# mbedWarp.net
KiCad netlist of a schematic drawn in EAGLE
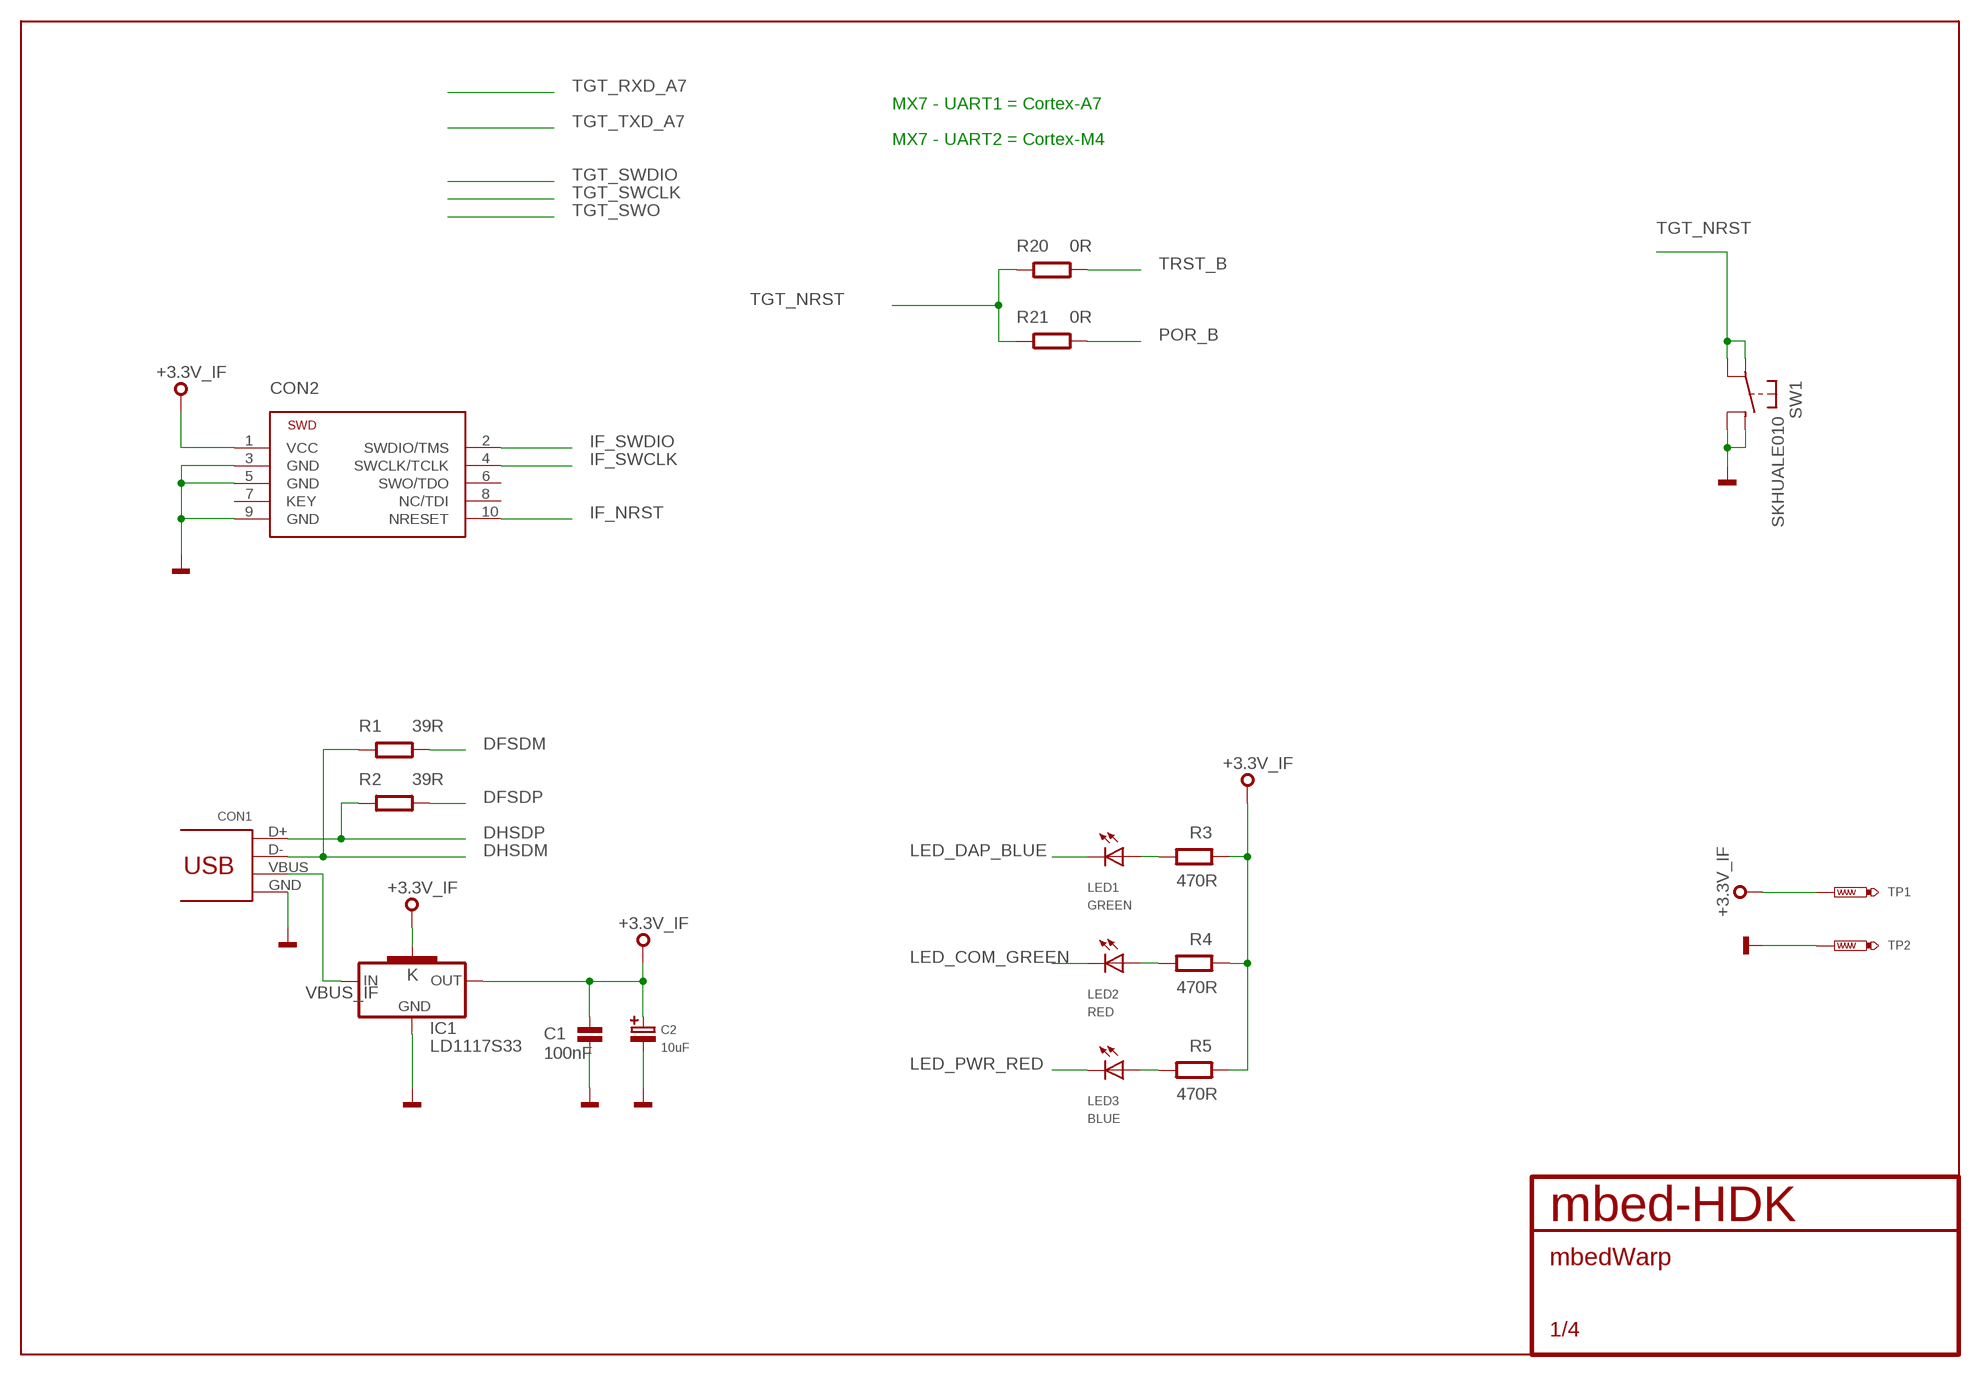
[diagram p0: schematic, sheet 1]
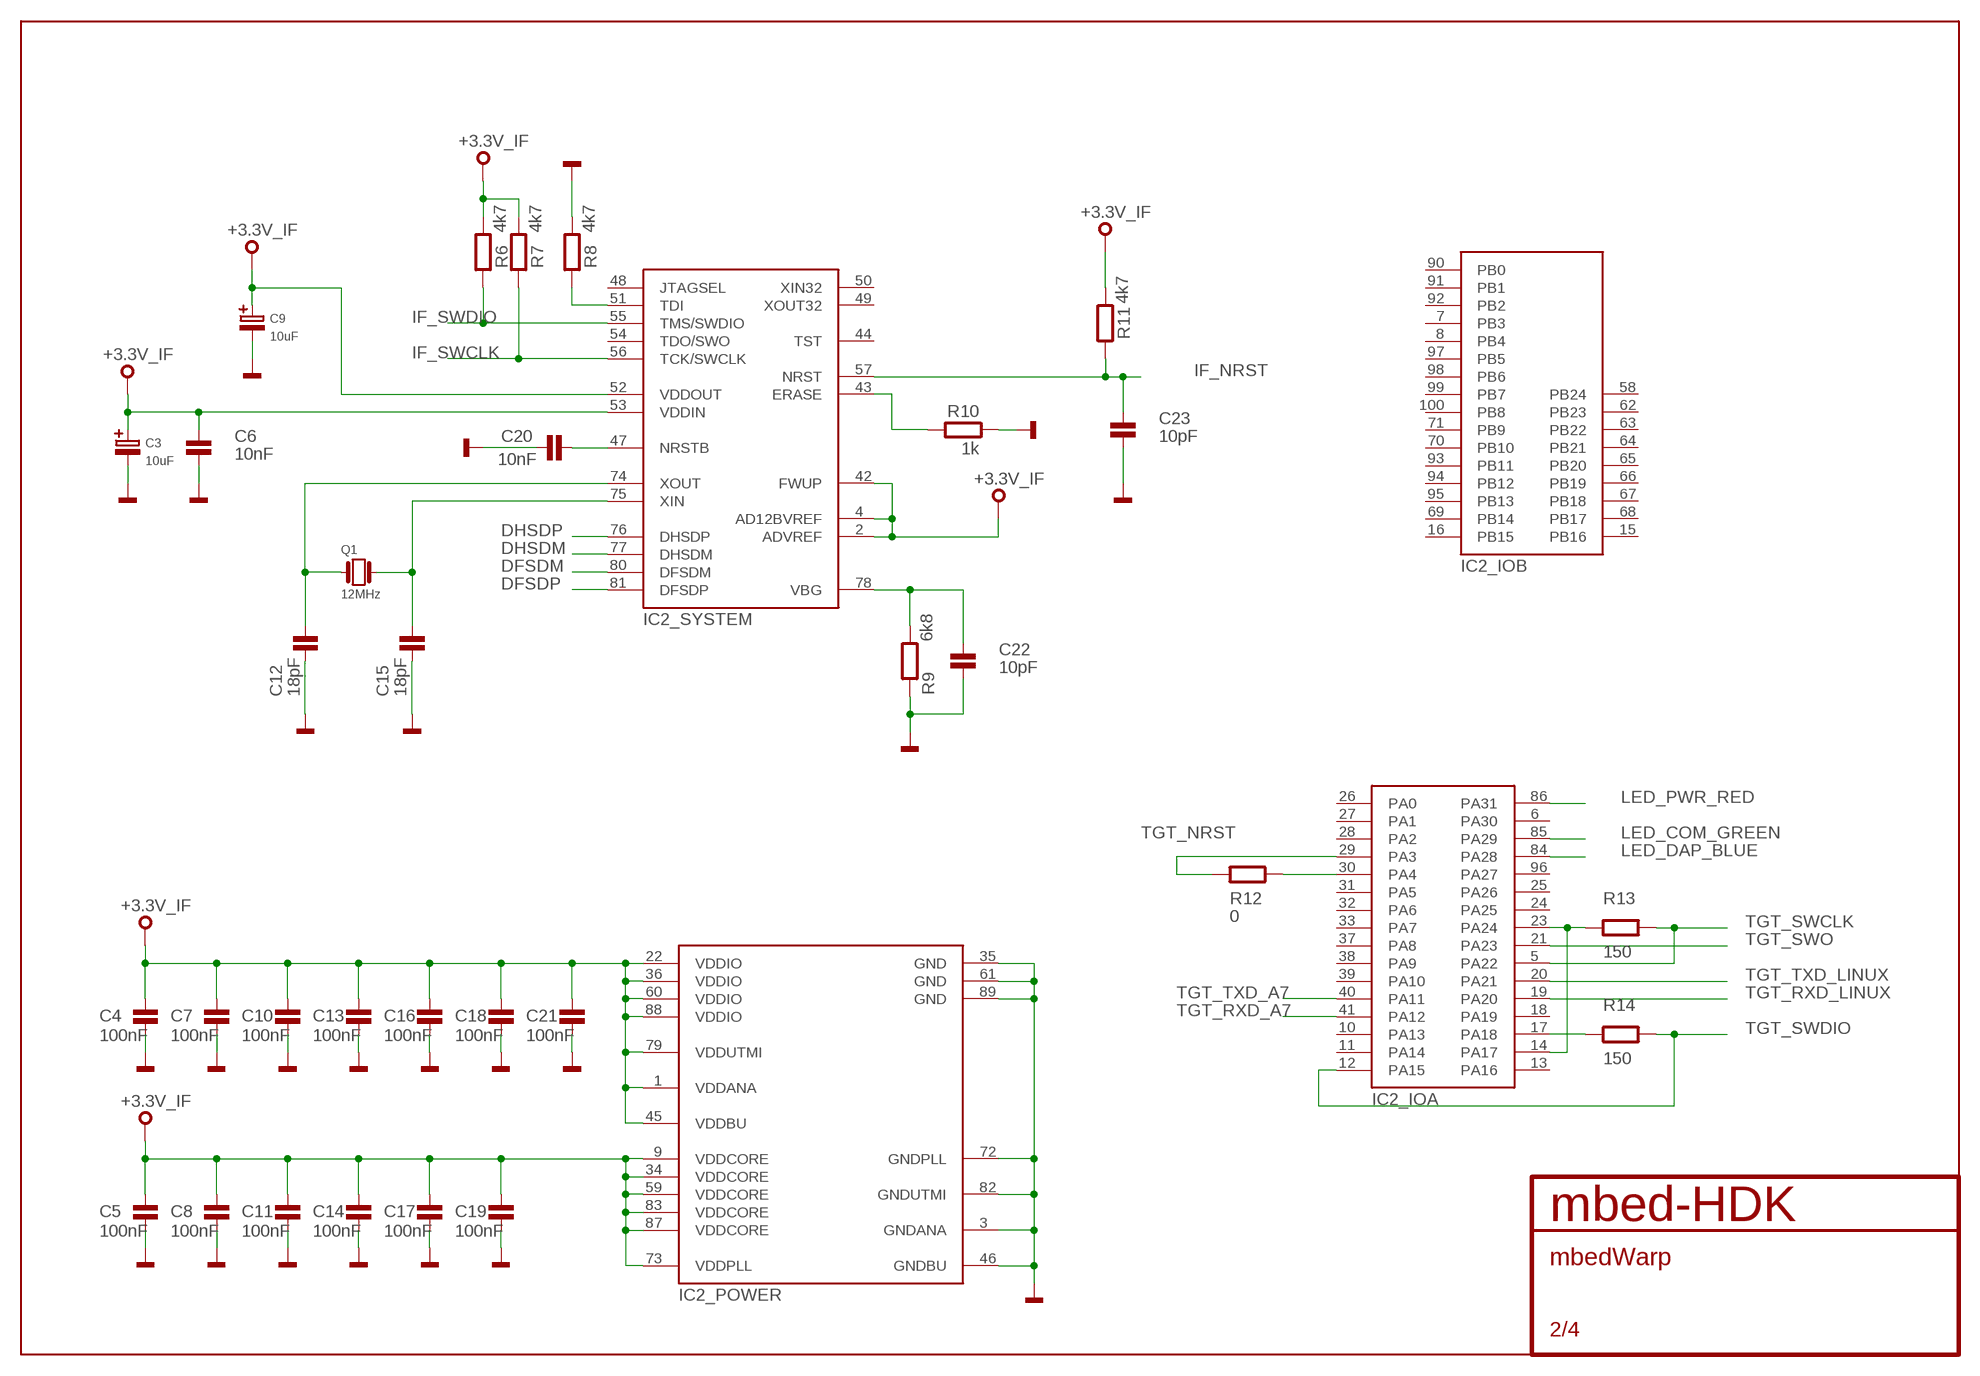
[diagram p1: schematic, sheet 2]
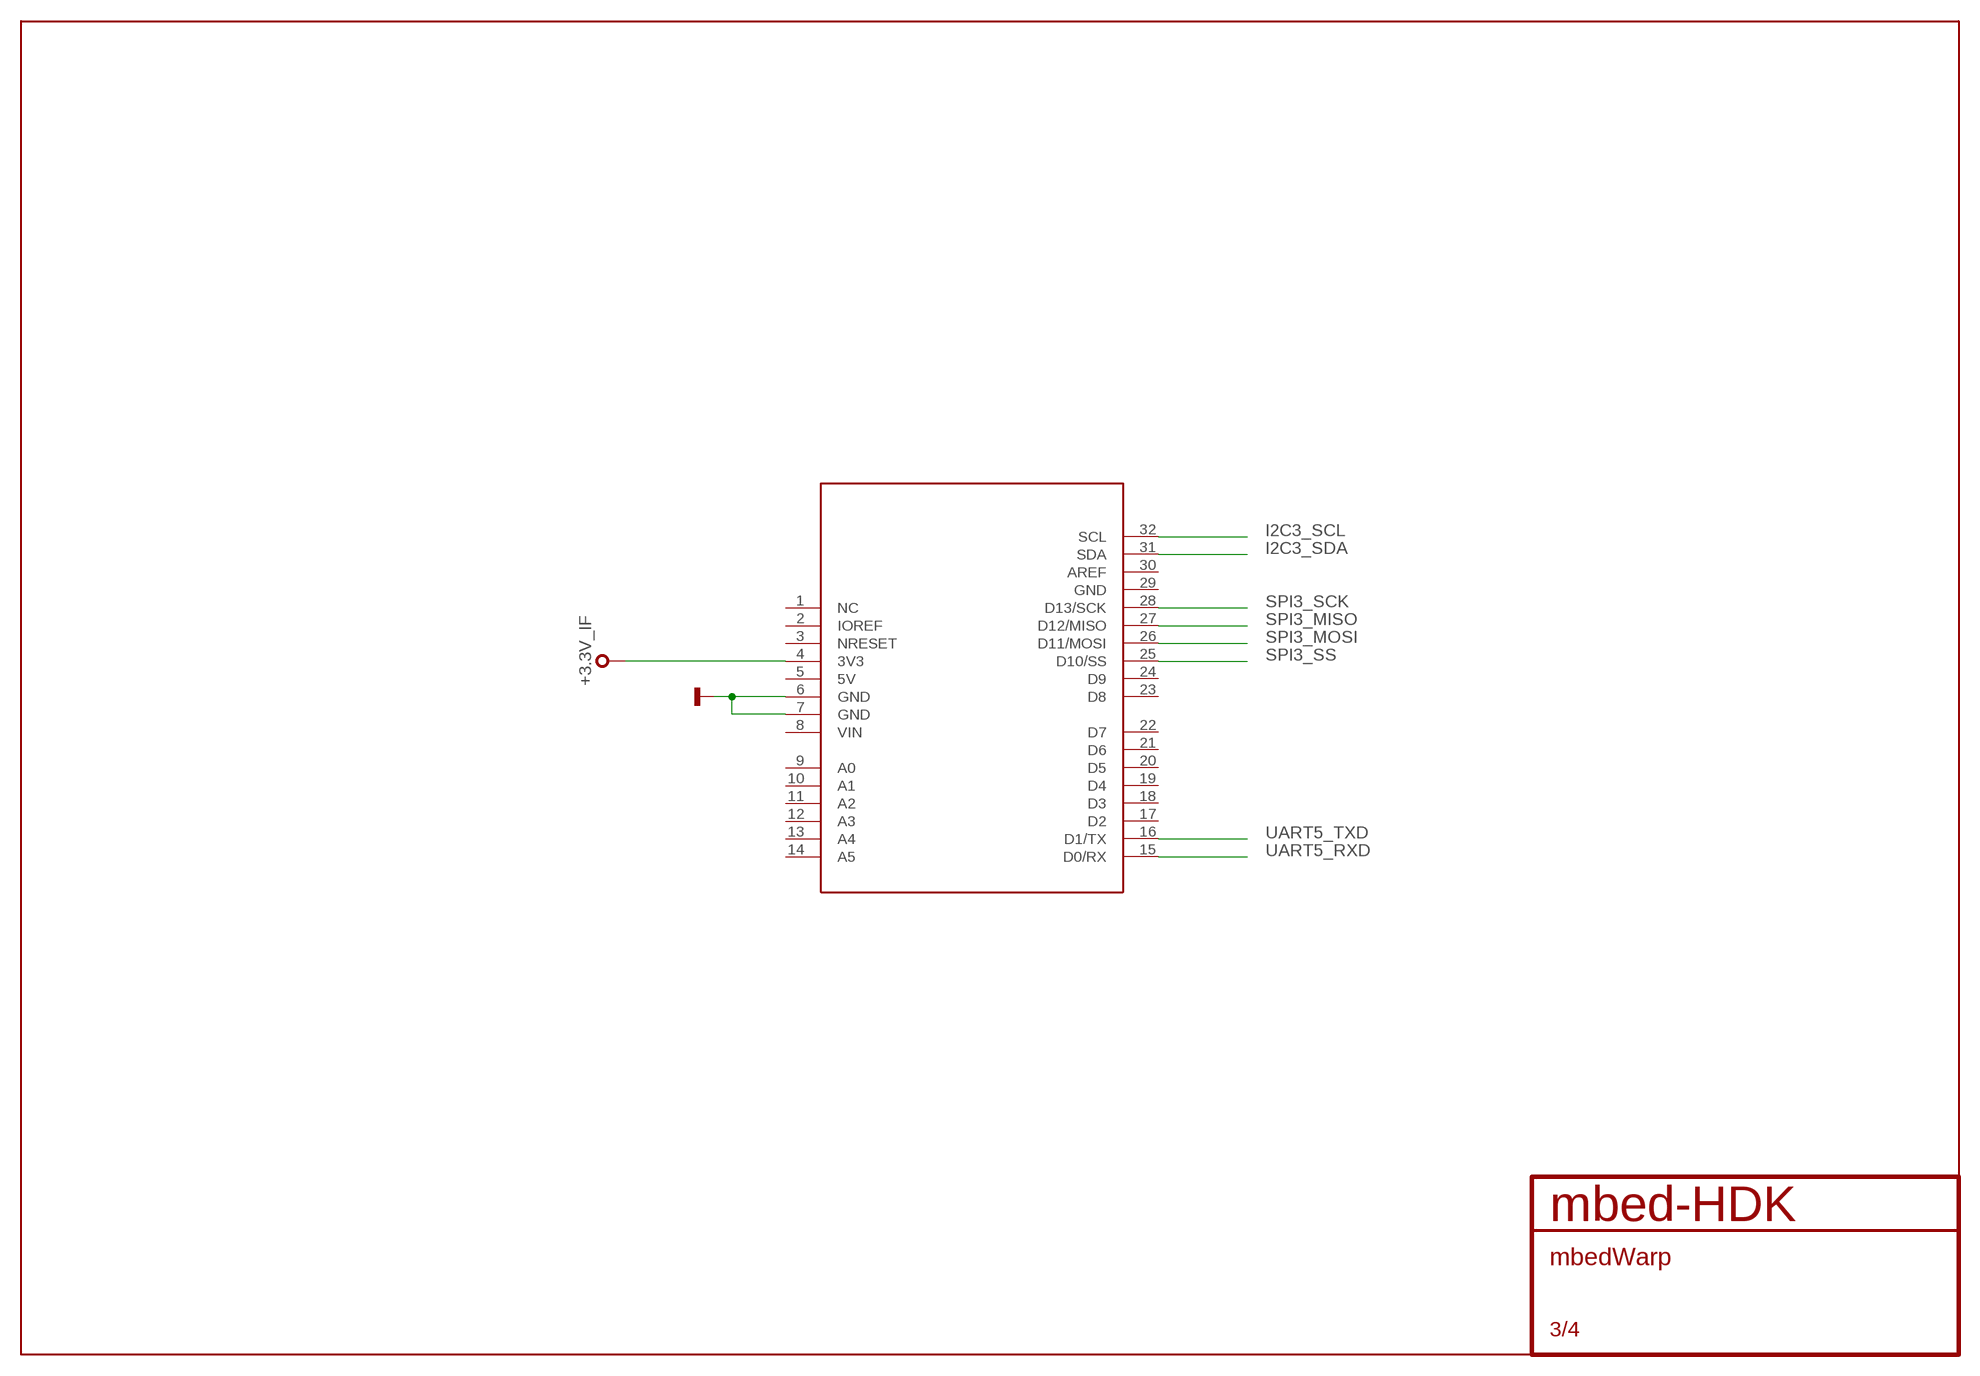
[diagram p2: schematic, sheet 3]
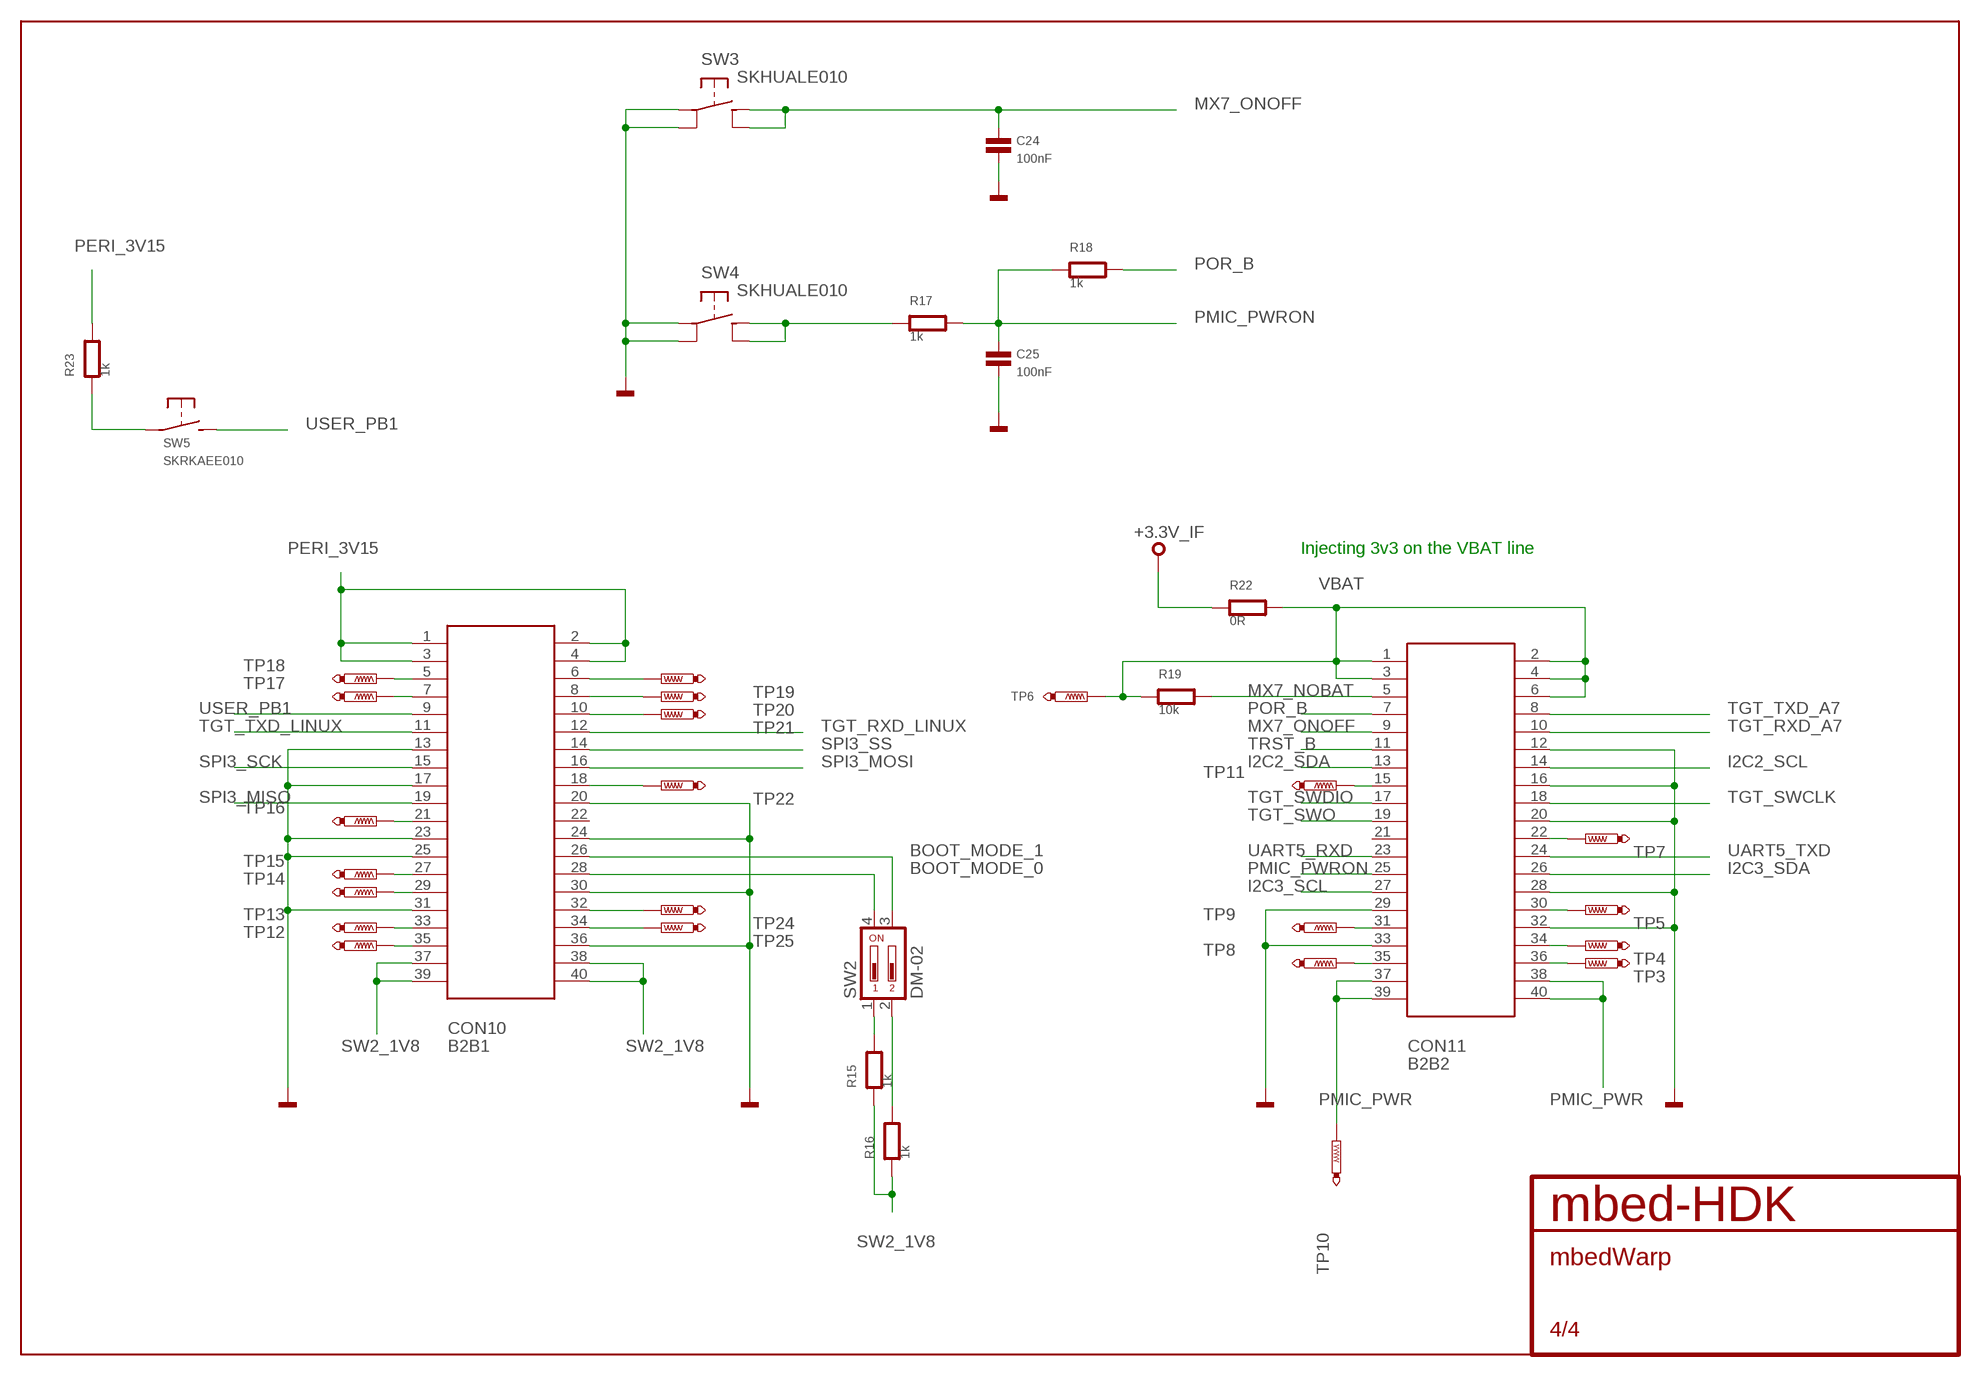
[diagram p3: schematic, sheet 4]

(export (version "E")
  (design (tool "Eeschema 10.0.6"))
  (components
    (comp (ref "C3")
      (value "10uF")
      (footprint "eagle-import:CASE-B")
      (libsource (lib "eagle-import") (part "C-POL_B"))
    )
    (comp (ref "C4")
      (value "100nF")
      (footprint "eagle-import:0603")
      (libsource (lib "eagle-import") (part "C0603"))
    )
    (comp (ref "C5")
      (value "100nF")
      (footprint "eagle-import:0603")
      (libsource (lib "eagle-import") (part "C0603"))
    )
    (comp (ref "C6")
      (value "10nF")
      (footprint "eagle-import:0603")
      (libsource (lib "eagle-import") (part "C0603"))
    )
    (comp (ref "C7")
      (value "100nF")
      (footprint "eagle-import:0603")
      (libsource (lib "eagle-import") (part "C0603"))
    )
    (comp (ref "C8")
      (value "100nF")
      (footprint "eagle-import:0603")
      (libsource (lib "eagle-import") (part "C0603"))
    )
    (comp (ref "C9")
      (value "10uF")
      (footprint "eagle-import:CASE-B")
      (libsource (lib "eagle-import") (part "C-POL_B"))
    )
    (comp (ref "C10")
      (value "100nF")
      (footprint "eagle-import:0603")
      (libsource (lib "eagle-import") (part "C0603"))
    )
    (comp (ref "C11")
      (value "100nF")
      (footprint "eagle-import:0603")
      (libsource (lib "eagle-import") (part "C0603"))
    )
    (comp (ref "C12")
      (value "18pF")
      (footprint "eagle-import:0603")
      (libsource (lib "eagle-import") (part "C0603"))
    )
    (comp (ref "C13")
      (value "100nF")
      (footprint "eagle-import:0603")
      (libsource (lib "eagle-import") (part "C0603"))
    )
    (comp (ref "C14")
      (value "100nF")
      (footprint "eagle-import:0603")
      (libsource (lib "eagle-import") (part "C0603"))
    )
    (comp (ref "C15")
      (value "18pF")
      (footprint "eagle-import:0603")
      (libsource (lib "eagle-import") (part "C0603"))
    )
    (comp (ref "C16")
      (value "100nF")
      (footprint "eagle-import:0603")
      (libsource (lib "eagle-import") (part "C0603"))
    )
    (comp (ref "C17")
      (value "100nF")
      (footprint "eagle-import:0603")
      (libsource (lib "eagle-import") (part "C0603"))
    )
    (comp (ref "C18")
      (value "100nF")
      (footprint "eagle-import:0603")
      (libsource (lib "eagle-import") (part "C0603"))
    )
    (comp (ref "C19")
      (value "100nF")
      (footprint "eagle-import:0603")
      (libsource (lib "eagle-import") (part "C0603"))
    )
    (comp (ref "C20")
      (value "10nF")
      (footprint "eagle-import:0603")
      (libsource (lib "eagle-import") (part "C0603"))
    )
    (comp (ref "C21")
      (value "100nF")
      (footprint "eagle-import:0603")
      (libsource (lib "eagle-import") (part "C0603"))
    )
    (comp (ref "C22")
      (value "10pF")
      (footprint "eagle-import:0603")
      (libsource (lib "eagle-import") (part "C0603"))
    )
    (comp (ref "C23")
      (value "10pF")
      (footprint "eagle-import:0603")
      (libsource (lib "eagle-import") (part "C0603"))
    )
    (comp (ref "IC2")
      (value "AT91SAM3U2CA")
      (footprint "eagle-import:LQFP100")
      (libsource (lib "eagle-import") (part "AT91SAM3U2CA"))
    )
    (comp (ref "Q1")
      (value "12MHz")
      (footprint "eagle-import:3.2X.2.5")
      (libsource (lib "eagle-import") (part "Q_3.2X2.5"))
    )
    (comp (ref "R6")
      (value "4k7")
      (footprint "eagle-import:0603")
      (libsource (lib "eagle-import") (part "R0603"))
    )
    (comp (ref "R7")
      (value "4k7")
      (footprint "eagle-import:0603")
      (libsource (lib "eagle-import") (part "R0603"))
    )
    (comp (ref "R8")
      (value "4k7")
      (footprint "eagle-import:0603")
      (libsource (lib "eagle-import") (part "R0603"))
    )
    (comp (ref "R9")
      (value "6k8")
      (footprint "eagle-import:0603")
      (libsource (lib "eagle-import") (part "R0603"))
    )
    (comp (ref "R10")
      (value "1k")
      (footprint "eagle-import:0603")
      (libsource (lib "eagle-import") (part "R0603"))
    )
    (comp (ref "R11")
      (value "4k7")
      (footprint "eagle-import:0603")
      (libsource (lib "eagle-import") (part "R0603"))
    )
    (comp (ref "R12")
      (value "0")
      (footprint "eagle-import:0603")
      (libsource (lib "eagle-import") (part "R0603"))
    )
    (comp (ref "R13")
      (value "150")
      (footprint "eagle-import:0603")
      (libsource (lib "eagle-import") (part "R0603"))
    )
    (comp (ref "R14")
      (value "150")
      (footprint "eagle-import:0603")
      (libsource (lib "eagle-import") (part "R0603"))
    )
    (comp (ref "C1")
      (value "100nF")
      (footprint "eagle-import:0603")
      (libsource (lib "eagle-import") (part "C0603"))
    )
    (comp (ref "C2")
      (value "10uF")
      (footprint "eagle-import:CASE-B")
      (libsource (lib "eagle-import") (part "C-POL_B"))
    )
    (comp (ref "CON1")
      (value "USB_MICROB")
      (footprint "eagle-import:MOLEX-47364-0001")
      (libsource (lib "eagle-import") (part "USB_MICROB"))
    )
    (comp (ref "CON2")
      (value "SWD-10-SMD")
      (footprint "eagle-import:SWD-10-SMD")
      (libsource (lib "eagle-import") (part "SWD-10-SMD"))
    )
    (comp (ref "IC1")
      (value "LD1117S33")
      (footprint "eagle-import:SOT223")
      (libsource (lib "eagle-import") (part "LD1117S33"))
    )
    (comp (ref "LED1")
      (value "GREEN")
      (footprint "eagle-import:CHIPLED_0603")
      (libsource (lib "eagle-import") (part "LED0603"))
    )
    (comp (ref "LED2")
      (value "RED")
      (footprint "eagle-import:CHIPLED_0603")
      (libsource (lib "eagle-import") (part "LED0603"))
    )
    (comp (ref "LED3")
      (value "BLUE")
      (footprint "eagle-import:CHIPLED_0603")
      (libsource (lib "eagle-import") (part "LED0603"))
    )
    (comp (ref "R1")
      (value "39R")
      (footprint "eagle-import:0603")
      (libsource (lib "eagle-import") (part "R0603"))
    )
    (comp (ref "R2")
      (value "39R")
      (footprint "eagle-import:0603")
      (libsource (lib "eagle-import") (part "R0603"))
    )
    (comp (ref "R3")
      (value "470R")
      (footprint "eagle-import:0603")
      (libsource (lib "eagle-import") (part "R0603"))
    )
    (comp (ref "R4")
      (value "470R")
      (footprint "eagle-import:0603")
      (libsource (lib "eagle-import") (part "R0603"))
    )
    (comp (ref "R5")
      (value "470R")
      (footprint "eagle-import:0603")
      (libsource (lib "eagle-import") (part "R0603"))
    )
    (comp (ref "R20")
      (value "0R")
      (footprint "eagle-import:0603")
      (libsource (lib "eagle-import") (part "R0603"))
    )
    (comp (ref "R21")
      (value "0R")
      (footprint "eagle-import:0603")
      (libsource (lib "eagle-import") (part "R0603"))
    )
    (comp (ref "SW1")
      (value "SKHUALE010")
      (footprint "eagle-import:SKHUALE010")
      (fields (field (name "MF") "ALPS"))
      (libsource (lib "eagle-import") (part "SKHUALE010"))
    )
    (comp (ref "TP1")
      (value "TEST-POINT-50R-PTH")
      (footprint "eagle-import:TP50-PTH")
      (libsource (lib "eagle-import") (part "TEST-POINT-50R-PTH"))
    )
    (comp (ref "TP2")
      (value "TEST-POINT-50R-PTH")
      (footprint "eagle-import:TP50-PTH")
      (libsource (lib "eagle-import") (part "TEST-POINT-50R-PTH"))
    )
    (comp (ref "BRD1")
      (value "ARDUINO-R3_SILK")
      (footprint "eagle-import:ARDUINO-R3-SILK")
      (libsource (lib "eagle-import") (part "ARDUINO-R3_SILK"))
    )
    (comp (ref "C24")
      (value "100nF")
      (footprint "eagle-import:0603")
      (libsource (lib "eagle-import") (part "CAPACITOR0603"))
    )
    (comp (ref "C25")
      (value "100nF")
      (footprint "eagle-import:0603")
      (libsource (lib "eagle-import") (part "CAPACITOR0603"))
    )
    (comp (ref "CON10")
      (value "B2B1")
      (footprint "eagle-import:DF40HC-XX-40DS-XX-V")
      (libsource (lib "eagle-import") (part "DF40HC-XX-40DS-XX-V"))
    )
    (comp (ref "CON11")
      (value "B2B2")
      (footprint "eagle-import:DF40HC-XX-40DS-XX-V")
      (libsource (lib "eagle-import") (part "DF40HC-XX-40DS-XX-V"))
    )
    (comp (ref "R15")
      (value "1k")
      (footprint "eagle-import:0603")
      (libsource (lib "eagle-import") (part "RESISTOR0603"))
    )
    (comp (ref "R16")
      (value "1k")
      (footprint "eagle-import:0603")
      (libsource (lib "eagle-import") (part "RESISTOR0603"))
    )
    (comp (ref "R17")
      (value "1k")
      (footprint "eagle-import:0603")
      (libsource (lib "eagle-import") (part "RESISTOR0603"))
    )
    (comp (ref "R18")
      (value "1k")
      (footprint "eagle-import:0603")
      (libsource (lib "eagle-import") (part "RESISTOR0603"))
    )
    (comp (ref "R19")
      (value "10k")
      (footprint "eagle-import:0603")
      (libsource (lib "eagle-import") (part "RESISTOR0603"))
    )
    (comp (ref "R22")
      (value "0R")
      (footprint "eagle-import:0603")
      (libsource (lib "eagle-import") (part "RESISTOR0603"))
    )
    (comp (ref "R23")
      (value "1k")
      (footprint "eagle-import:0603")
      (libsource (lib "eagle-import") (part "RESISTOR0603"))
    )
    (comp (ref "SW2")
      (value "DM-02")
      (footprint "eagle-import:DM-02")
      (libsource (lib "eagle-import") (part "DM-02"))
    )
    (comp (ref "SW3")
      (value "SKHUALE010")
      (footprint "eagle-import:SKHUALE010")
      (fields (field (name "MF") "ALPS"))
      (libsource (lib "eagle-import") (part "SKHUALE010"))
    )
    (comp (ref "SW4")
      (value "SKHUALE010")
      (footprint "eagle-import:SKHUALE010")
      (fields (field (name "MF") "ALPS"))
      (libsource (lib "eagle-import") (part "SKHUALE010"))
    )
    (comp (ref "SW5")
      (value "SKRKAEE010")
      (footprint "eagle-import:SKRKAEE010")
      (fields (field (name "MF") "ALPS"))
      (libsource (lib "eagle-import") (part "SKRKAEE010"))
    )
    (comp (ref "TP3")
      (value "PTR1TP06R")
      (footprint "eagle-import:TP06R")
      (libsource (lib "eagle-import") (part "PTR1TP06R"))
    )
    (comp (ref "TP4")
      (value "PTR1TP06R")
      (footprint "eagle-import:TP06R")
      (libsource (lib "eagle-import") (part "PTR1TP06R"))
    )
    (comp (ref "TP5")
      (value "PTR1TP06R")
      (footprint "eagle-import:TP06R")
      (libsource (lib "eagle-import") (part "PTR1TP06R"))
    )
    (comp (ref "TP6")
      (value "TEST-POINT-50R-SMD")
      (footprint "eagle-import:TP50-SMD")
      (libsource (lib "eagle-import") (part "TEST-POINT-50R-SMD"))
    )
    (comp (ref "TP7")
      (value "PTR1TP06R")
      (footprint "eagle-import:TP06R")
      (libsource (lib "eagle-import") (part "PTR1TP06R"))
    )
    (comp (ref "TP8")
      (value "PTR1TP06R")
      (footprint "eagle-import:TP06R")
      (libsource (lib "eagle-import") (part "PTR1TP06R"))
    )
    (comp (ref "TP9")
      (value "PTR1TP06R")
      (footprint "eagle-import:TP06R")
      (libsource (lib "eagle-import") (part "PTR1TP06R"))
    )
    (comp (ref "TP10")
      (value "PTR1TP06R")
      (footprint "eagle-import:TP06R")
      (libsource (lib "eagle-import") (part "PTR1TP06R"))
    )
    (comp (ref "TP11")
      (value "PTR1TP06R")
      (footprint "eagle-import:TP06R")
      (libsource (lib "eagle-import") (part "PTR1TP06R"))
    )
    (comp (ref "TP12")
      (value "PTR1TP06R")
      (footprint "eagle-import:TP06R")
      (libsource (lib "eagle-import") (part "PTR1TP06R"))
    )
    (comp (ref "TP13")
      (value "PTR1TP06R")
      (footprint "eagle-import:TP06R")
      (libsource (lib "eagle-import") (part "PTR1TP06R"))
    )
    (comp (ref "TP14")
      (value "PTR1TP06R")
      (footprint "eagle-import:TP06R")
      (libsource (lib "eagle-import") (part "PTR1TP06R"))
    )
    (comp (ref "TP15")
      (value "PTR1TP06R")
      (footprint "eagle-import:TP06R")
      (libsource (lib "eagle-import") (part "PTR1TP06R"))
    )
    (comp (ref "TP16")
      (value "PTR1TP06R")
      (footprint "eagle-import:TP06R")
      (libsource (lib "eagle-import") (part "PTR1TP06R"))
    )
    (comp (ref "TP17")
      (value "PTR1TP06R")
      (footprint "eagle-import:TP06R")
      (libsource (lib "eagle-import") (part "PTR1TP06R"))
    )
    (comp (ref "TP18")
      (value "PTR1TP06R")
      (footprint "eagle-import:TP06R")
      (libsource (lib "eagle-import") (part "PTR1TP06R"))
    )
    (comp (ref "TP19")
      (value "PTR1TP06R")
      (footprint "eagle-import:TP06R")
      (libsource (lib "eagle-import") (part "PTR1TP06R"))
    )
    (comp (ref "TP20")
      (value "PTR1TP06R")
      (footprint "eagle-import:TP06R")
      (libsource (lib "eagle-import") (part "PTR1TP06R"))
    )
    (comp (ref "TP21")
      (value "PTR1TP06R")
      (footprint "eagle-import:TP06R")
      (libsource (lib "eagle-import") (part "PTR1TP06R"))
    )
    (comp (ref "TP22")
      (value "PTR1TP06R")
      (footprint "eagle-import:TP06R")
      (libsource (lib "eagle-import") (part "PTR1TP06R"))
    )
    (comp (ref "TP24")
      (value "PTR1TP06R")
      (footprint "eagle-import:TP06R")
      (libsource (lib "eagle-import") (part "PTR1TP06R"))
    )
    (comp (ref "TP25")
      (value "PTR1TP06R")
      (footprint "eagle-import:TP06R")
      (libsource (lib "eagle-import") (part "PTR1TP06R"))
    )
  )
  (nets
    (net (code "1") (name "+3.3V_IF") (class "Default")
      (node (ref "BRD1") (pin "4") (pinfunction "3V3_4") (pintype "bidirectional"))
      (node (ref "C1") (pin "1") (pinfunction "P$1_1") (pintype "passive"))
      (node (ref "C10") (pin "1") (pinfunction "P$1_1") (pintype "passive"))
      (node (ref "C11") (pin "1") (pinfunction "P$1_1") (pintype "passive"))
      (node (ref "C13") (pin "1") (pinfunction "P$1_1") (pintype "passive"))
      (node (ref "C14") (pin "1") (pinfunction "P$1_1") (pintype "passive"))
      (node (ref "C16") (pin "1") (pinfunction "P$1_1") (pintype "passive"))
      (node (ref "C17") (pin "1") (pinfunction "P$1_1") (pintype "passive"))
      (node (ref "C18") (pin "1") (pinfunction "P$1_1") (pintype "passive"))
      (node (ref "C19") (pin "1") (pinfunction "P$1_1") (pintype "passive"))
      (node (ref "C2") (pin "1") (pinfunction "1_1") (pintype "passive"))
      (node (ref "C21") (pin "1") (pinfunction "P$1_1") (pintype "passive"))
      (node (ref "C3") (pin "1") (pinfunction "1_1") (pintype "passive"))
      (node (ref "C4") (pin "1") (pinfunction "P$1_1") (pintype "passive"))
      (node (ref "C5") (pin "1") (pinfunction "P$1_1") (pintype "passive"))
      (node (ref "C6") (pin "1") (pinfunction "P$1_1") (pintype "passive"))
      (node (ref "C7") (pin "1") (pinfunction "P$1_1") (pintype "passive"))
      (node (ref "C8") (pin "1") (pinfunction "P$1_1") (pintype "passive"))
      (node (ref "C9") (pin "1") (pinfunction "1_1") (pintype "passive"))
      (node (ref "CON2") (pin "1") (pinfunction "VCC_1") (pintype "bidirectional"))
      (node (ref "IC1") (pin "2") (pinfunction "OUT_2") (pintype "passive"))
      (node (ref "IC1") (pin "4") (pinfunction "K_4") (pintype "passive"))
      (node (ref "IC2") (pin "1") (pinfunction "VDDANA_1") (pintype "bidirectional"))
      (node (ref "IC2") (pin "2") (pinfunction "ADVREF_2") (pintype "bidirectional"))
      (node (ref "IC2") (pin "22") (pinfunction "VDDIO_22") (pintype "bidirectional"))
      (node (ref "IC2") (pin "34") (pinfunction "VDDCORE_34") (pintype "bidirectional"))
      (node (ref "IC2") (pin "36") (pinfunction "VDDIO_36") (pintype "bidirectional"))
      (node (ref "IC2") (pin "4") (pinfunction "AD12BVREF_4") (pintype "bidirectional"))
      (node (ref "IC2") (pin "42") (pinfunction "FWUP_42") (pintype "bidirectional"))
      (node (ref "IC2") (pin "45") (pinfunction "VDDBU_45") (pintype "bidirectional"))
      (node (ref "IC2") (pin "52") (pinfunction "VDDOUT_52") (pintype "bidirectional"))
      (node (ref "IC2") (pin "53") (pinfunction "VDDIN_53") (pintype "bidirectional"))
      (node (ref "IC2") (pin "59") (pinfunction "VDDCORE_59") (pintype "bidirectional"))
      (node (ref "IC2") (pin "60") (pinfunction "VDDIO_60") (pintype "bidirectional"))
      (node (ref "IC2") (pin "73") (pinfunction "VDDPLL_73") (pintype "bidirectional"))
      (node (ref "IC2") (pin "79") (pinfunction "VDDUTMI_79") (pintype "bidirectional"))
      (node (ref "IC2") (pin "83") (pinfunction "VDDCORE_83") (pintype "bidirectional"))
      (node (ref "IC2") (pin "87") (pinfunction "VDDCORE_87") (pintype "bidirectional"))
      (node (ref "IC2") (pin "88") (pinfunction "VDDIO_88") (pintype "bidirectional"))
      (node (ref "IC2") (pin "9") (pinfunction "VDDCORE_9") (pintype "bidirectional"))
      (node (ref "R11") (pin "2") (pinfunction "P$2_2") (pintype "passive"))
      (node (ref "R22") (pin "1") (pinfunction "P$1_1") (pintype "passive"))
      (node (ref "R3") (pin "1") (pinfunction "P$1_1") (pintype "passive"))
      (node (ref "R4") (pin "1") (pinfunction "P$1_1") (pintype "passive"))
      (node (ref "R5") (pin "1") (pinfunction "P$1_1") (pintype "passive"))
      (node (ref "R6") (pin "2") (pinfunction "P$2_2") (pintype "passive"))
      (node (ref "R7") (pin "2") (pinfunction "P$2_2") (pintype "passive"))
      (node (ref "TP1") (pin "TP") (pinfunction "TP_TP") (pintype "input"))
    )
    (net (code "2") (name "BOOT_MODE_0") (class "Default")
      (node (ref "CON10") (pin "28") (pinfunction "P$28_28") (pintype "bidirectional"))
      (node (ref "SW2") (pin "4") (pinfunction "4_4") (pintype "passive"))
    )
    (net (code "3") (name "BOOT_MODE_1") (class "Default")
      (node (ref "CON10") (pin "26") (pinfunction "P$26_26") (pintype "bidirectional"))
      (node (ref "SW2") (pin "3") (pinfunction "3_3") (pintype "passive"))
    )
    (net (code "4") (name "DFSDM") (class "Default")
      (node (ref "IC2") (pin "80") (pinfunction "DFSDM_80") (pintype "bidirectional"))
      (node (ref "R1") (pin "2") (pinfunction "P$2_2") (pintype "passive"))
    )
    (net (code "5") (name "DFSDP") (class "Default")
      (node (ref "IC2") (pin "81") (pinfunction "DFSDP_81") (pintype "bidirectional"))
      (node (ref "R2") (pin "2") (pinfunction "P$2_2") (pintype "passive"))
    )
    (net (code "6") (name "DHSDM") (class "Default")
      (node (ref "CON1") (pin "D-") (pinfunction "D-_D-") (pintype "bidirectional"))
      (node (ref "IC2") (pin "77") (pinfunction "DHSDM_77") (pintype "bidirectional"))
      (node (ref "R1") (pin "1") (pinfunction "P$1_1") (pintype "passive"))
    )
    (net (code "7") (name "DHSDP") (class "Default")
      (node (ref "CON1") (pin "D+") (pinfunction "D+_D+") (pintype "bidirectional"))
      (node (ref "IC2") (pin "76") (pinfunction "DHSDP_76") (pintype "bidirectional"))
      (node (ref "R2") (pin "1") (pinfunction "P$1_1") (pintype "passive"))
    )
    (net (code "8") (name "GND") (class "Default")
      (node (ref "BRD1") (pin "6") (pinfunction "GND_6") (pintype "bidirectional"))
      (node (ref "BRD1") (pin "7") (pinfunction "GND_7") (pintype "bidirectional"))
      (node (ref "C1") (pin "2") (pinfunction "P$2_2") (pintype "passive"))
      (node (ref "C10") (pin "2") (pinfunction "P$2_2") (pintype "passive"))
      (node (ref "C11") (pin "2") (pinfunction "P$2_2") (pintype "passive"))
      (node (ref "C12") (pin "2") (pinfunction "P$2_2") (pintype "passive"))
      (node (ref "C13") (pin "2") (pinfunction "P$2_2") (pintype "passive"))
      (node (ref "C14") (pin "2") (pinfunction "P$2_2") (pintype "passive"))
      (node (ref "C15") (pin "2") (pinfunction "P$2_2") (pintype "passive"))
      (node (ref "C16") (pin "2") (pinfunction "P$2_2") (pintype "passive"))
      (node (ref "C17") (pin "2") (pinfunction "P$2_2") (pintype "passive"))
      (node (ref "C18") (pin "2") (pinfunction "P$2_2") (pintype "passive"))
      (node (ref "C19") (pin "2") (pinfunction "P$2_2") (pintype "passive"))
      (node (ref "C2") (pin "2") (pinfunction "2_2") (pintype "passive"))
      (node (ref "C20") (pin "2") (pinfunction "P$2_2") (pintype "passive"))
      (node (ref "C21") (pin "2") (pinfunction "P$2_2") (pintype "passive"))
      (node (ref "C22") (pin "2") (pinfunction "P$2_2") (pintype "passive"))
      (node (ref "C23") (pin "2") (pinfunction "P$2_2") (pintype "passive"))
      (node (ref "C24") (pin "2") (pinfunction "P$2_2") (pintype "passive"))
      (node (ref "C25") (pin "2") (pinfunction "P$2_2") (pintype "passive"))
      (node (ref "C3") (pin "2") (pinfunction "2_2") (pintype "passive"))
      (node (ref "C4") (pin "2") (pinfunction "P$2_2") (pintype "passive"))
      (node (ref "C5") (pin "2") (pinfunction "P$2_2") (pintype "passive"))
      (node (ref "C6") (pin "2") (pinfunction "P$2_2") (pintype "passive"))
      (node (ref "C7") (pin "2") (pinfunction "P$2_2") (pintype "passive"))
      (node (ref "C8") (pin "2") (pinfunction "P$2_2") (pintype "passive"))
      (node (ref "C9") (pin "2") (pinfunction "2_2") (pintype "passive"))
      (node (ref "CON1") (pin "GND") (pinfunction "GND_GND") (pintype "bidirectional"))
      (node (ref "CON10") (pin "13") (pinfunction "P$13_13") (pintype "bidirectional"))
      (node (ref "CON10") (pin "17") (pinfunction "P$17_17") (pintype "bidirectional"))
      (node (ref "CON10") (pin "20") (pinfunction "P$20_20") (pintype "bidirectional"))
      (node (ref "CON10") (pin "23") (pinfunction "P$23_23") (pintype "bidirectional"))
      (node (ref "CON10") (pin "24") (pinfunction "P$24_24") (pintype "bidirectional"))
      (node (ref "CON10") (pin "25") (pinfunction "P$25_25") (pintype "bidirectional"))
      (node (ref "CON10") (pin "30") (pinfunction "P$30_30") (pintype "bidirectional"))
      (node (ref "CON10") (pin "31") (pinfunction "P$31_31") (pintype "bidirectional"))
      (node (ref "CON10") (pin "36") (pinfunction "P$36_36") (pintype "bidirectional"))
      (node (ref "CON11") (pin "12") (pinfunction "P$12_12") (pintype "bidirectional"))
      (node (ref "CON11") (pin "16") (pinfunction "P$16_16") (pintype "bidirectional"))
      (node (ref "CON11") (pin "20") (pinfunction "P$20_20") (pintype "bidirectional"))
      (node (ref "CON11") (pin "28") (pinfunction "P$28_28") (pintype "bidirectional"))
      (node (ref "CON11") (pin "29") (pinfunction "P$29_29") (pintype "bidirectional"))
      (node (ref "CON11") (pin "32") (pinfunction "P$32_32") (pintype "bidirectional"))
      (node (ref "CON11") (pin "33") (pinfunction "P$33_33") (pintype "bidirectional"))
      (node (ref "CON2") (pin "3") (pinfunction "GND_3") (pintype "bidirectional"))
      (node (ref "CON2") (pin "5") (pinfunction "GND_5") (pintype "bidirectional"))
      (node (ref "CON2") (pin "9") (pinfunction "GND_9") (pintype "bidirectional"))
      (node (ref "IC1") (pin "1") (pinfunction "GND_1") (pintype "input"))
      (node (ref "IC2") (pin "3") (pinfunction "GNDANA_3") (pintype "bidirectional"))
      (node (ref "IC2") (pin "35") (pinfunction "GND_35") (pintype "bidirectional"))
      (node (ref "IC2") (pin "46") (pinfunction "GNDBU_46") (pintype "bidirectional"))
      (node (ref "IC2") (pin "61") (pinfunction "GND_61") (pintype "bidirectional"))
      (node (ref "IC2") (pin "72") (pinfunction "GNDPLL_72") (pintype "bidirectional"))
      (node (ref "IC2") (pin "82") (pinfunction "GNDUTMI_82") (pintype "bidirectional"))
      (node (ref "IC2") (pin "89") (pinfunction "GND_89") (pintype "bidirectional"))
      (node (ref "R10") (pin "1") (pinfunction "P$1_1") (pintype "passive"))
      (node (ref "R8") (pin "2") (pinfunction "P$2_2") (pintype "passive"))
      (node (ref "R9") (pin "1") (pinfunction "P$1_1") (pintype "passive"))
      (node (ref "SW1") (pin "P$3") (pinfunction "B1_P$3") (pintype "passive"))
      (node (ref "SW1") (pin "P$4") (pinfunction "B2_P$4") (pintype "passive"))
      (node (ref "SW3") (pin "P$1") (pinfunction "A1_P$1") (pintype "passive"))
      (node (ref "SW3") (pin "P$2") (pinfunction "A2_P$2") (pintype "passive"))
      (node (ref "SW4") (pin "P$1") (pinfunction "A1_P$1") (pintype "passive"))
      (node (ref "SW4") (pin "P$2") (pinfunction "A2_P$2") (pintype "passive"))
      (node (ref "TP2") (pin "TP") (pinfunction "TP_TP") (pintype "input"))
    )
    (net (code "9") (name "I2C2_SCL") (class "Default")
      (node (ref "CON11") (pin "14") (pinfunction "P$14_14") (pintype "bidirectional"))
    )
    (net (code "10") (name "I2C2_SDA") (class "Default")
      (node (ref "CON11") (pin "13") (pinfunction "P$13_13") (pintype "bidirectional"))
    )
    (net (code "11") (name "I2C3_SCL") (class "Default")
      (node (ref "BRD1") (pin "32") (pinfunction "SCL_32") (pintype "bidirectional"))
      (node (ref "CON11") (pin "27") (pinfunction "P$27_27") (pintype "bidirectional"))
    )
    (net (code "12") (name "I2C3_SDA") (class "Default")
      (node (ref "BRD1") (pin "31") (pinfunction "SDA_31") (pintype "bidirectional"))
      (node (ref "CON11") (pin "26") (pinfunction "P$26_26") (pintype "bidirectional"))
    )
    (net (code "13") (name "IF_NRST") (class "Default")
      (node (ref "C23") (pin "1") (pinfunction "P$1_1") (pintype "passive"))
      (node (ref "CON2") (pin "10") (pinfunction "NRESET_10") (pintype "bidirectional"))
      (node (ref "IC2") (pin "57") (pinfunction "NRST_57") (pintype "bidirectional"))
      (node (ref "R11") (pin "1") (pinfunction "P$1_1") (pintype "passive"))
    )
    (net (code "14") (name "IF_SWCLK") (class "Default")
      (node (ref "CON2") (pin "4") (pinfunction "SWCLK/TCLK_4") (pintype "bidirectional"))
      (node (ref "IC2") (pin "56") (pinfunction "TCK/SWCLK_56") (pintype "bidirectional"))
      (node (ref "R7") (pin "1") (pinfunction "P$1_1") (pintype "passive"))
    )
    (net (code "15") (name "IF_SWDIO") (class "Default")
      (node (ref "CON2") (pin "2") (pinfunction "SWDIO/TMS_2") (pintype "bidirectional"))
      (node (ref "IC2") (pin "55") (pinfunction "TMS/SWDIO_55") (pintype "bidirectional"))
      (node (ref "R6") (pin "1") (pinfunction "P$1_1") (pintype "passive"))
    )
    (net (code "16") (name "LED_COM_GREEN") (class "Default")
      (node (ref "IC2") (pin "85") (pinfunction "PA29_85") (pintype "bidirectional"))
      (node (ref "LED2") (pin "C") (pinfunction "C_C") (pintype "passive"))
    )
    (net (code "17") (name "LED_DAP_BLUE") (class "Default")
      (node (ref "IC2") (pin "84") (pinfunction "PA28_84") (pintype "bidirectional"))
      (node (ref "LED1") (pin "C") (pinfunction "C_C") (pintype "passive"))
    )
    (net (code "18") (name "LED_PWR_RED") (class "Default")
      (node (ref "IC2") (pin "86") (pinfunction "PA31_86") (pintype "bidirectional"))
      (node (ref "LED3") (pin "C") (pinfunction "C_C") (pintype "passive"))
    )
    (net (code "19") (name "MX7_NOBAT") (class "Default")
      (node (ref "CON11") (pin "5") (pinfunction "P$5_5") (pintype "bidirectional"))
      (node (ref "R19") (pin "2") (pinfunction "P$2_2") (pintype "passive"))
    )
    (net (code "20") (name "MX7_ONOFF") (class "Default")
      (node (ref "C24") (pin "1") (pinfunction "P$1_1") (pintype "passive"))
      (node (ref "CON11") (pin "9") (pinfunction "P$9_9") (pintype "bidirectional"))
      (node (ref "SW3") (pin "P$3") (pinfunction "B1_P$3") (pintype "passive"))
      (node (ref "SW3") (pin "P$4") (pinfunction "B2_P$4") (pintype "passive"))
    )
    (net (code "21") (name "Net-(C12-P$1)") (class "Default")
      (node (ref "C12") (pin "1") (pinfunction "P$1_1") (pintype "passive"))
      (node (ref "IC2") (pin "74") (pinfunction "XOUT_74") (pintype "bidirectional"))
      (node (ref "Q1") (pin "P$1") (pinfunction "1_P$1") (pintype "passive"))
    )
    (net (code "22") (name "Net-(C15-P$1)") (class "Default")
      (node (ref "C15") (pin "1") (pinfunction "P$1_1") (pintype "passive"))
      (node (ref "IC2") (pin "75") (pinfunction "XIN_75") (pintype "bidirectional"))
      (node (ref "Q1") (pin "P$3") (pinfunction "2_P$3") (pintype "passive"))
    )
    (net (code "23") (name "Net-(C20-P$1)") (class "Default")
      (node (ref "C20") (pin "1") (pinfunction "P$1_1") (pintype "passive"))
      (node (ref "IC2") (pin "47") (pinfunction "NRSTB_47") (pintype "bidirectional"))
    )
    (net (code "24") (name "Net-(C22-P$1)") (class "Default")
      (node (ref "C22") (pin "1") (pinfunction "P$1_1") (pintype "passive"))
      (node (ref "IC2") (pin "78") (pinfunction "VBG_78") (pintype "bidirectional"))
      (node (ref "R9") (pin "2") (pinfunction "P$2_2") (pintype "passive"))
    )
    (net (code "25") (name "Net-(CON10-P$5)") (class "Default")
      (node (ref "CON10") (pin "5") (pinfunction "P$5_5") (pintype "bidirectional"))
      (node (ref "TP18") (pin "TP") (pinfunction "TP_TP") (pintype "input"))
    )
    (net (code "26") (name "Net-(CON10-P$6)") (class "Default")
      (node (ref "CON10") (pin "6") (pinfunction "P$6_6") (pintype "bidirectional"))
      (node (ref "TP19") (pin "TP") (pinfunction "TP_TP") (pintype "input"))
    )
    (net (code "27") (name "Net-(CON10-P$7)") (class "Default")
      (node (ref "CON10") (pin "7") (pinfunction "P$7_7") (pintype "bidirectional"))
      (node (ref "TP17") (pin "TP") (pinfunction "TP_TP") (pintype "input"))
    )
    (net (code "28") (name "Net-(CON10-P$8)") (class "Default")
      (node (ref "CON10") (pin "8") (pinfunction "P$8_8") (pintype "bidirectional"))
      (node (ref "TP20") (pin "TP") (pinfunction "TP_TP") (pintype "input"))
    )
    (net (code "29") (name "Net-(CON10-P$10)") (class "Default")
      (node (ref "CON10") (pin "10") (pinfunction "P$10_10") (pintype "bidirectional"))
      (node (ref "TP21") (pin "TP") (pinfunction "TP_TP") (pintype "input"))
    )
    (net (code "30") (name "Net-(CON10-P$18)") (class "Default")
      (node (ref "CON10") (pin "18") (pinfunction "P$18_18") (pintype "bidirectional"))
      (node (ref "TP22") (pin "TP") (pinfunction "TP_TP") (pintype "input"))
    )
    (net (code "31") (name "Net-(CON10-P$21)") (class "Default")
      (node (ref "CON10") (pin "21") (pinfunction "P$21_21") (pintype "bidirectional"))
      (node (ref "TP16") (pin "TP") (pinfunction "TP_TP") (pintype "input"))
    )
    (net (code "32") (name "Net-(CON10-P$27)") (class "Default")
      (node (ref "CON10") (pin "27") (pinfunction "P$27_27") (pintype "bidirectional"))
      (node (ref "TP15") (pin "TP") (pinfunction "TP_TP") (pintype "input"))
    )
    (net (code "33") (name "Net-(CON10-P$29)") (class "Default")
      (node (ref "CON10") (pin "29") (pinfunction "P$29_29") (pintype "bidirectional"))
      (node (ref "TP14") (pin "TP") (pinfunction "TP_TP") (pintype "input"))
    )
    (net (code "34") (name "Net-(CON10-P$32)") (class "Default")
      (node (ref "CON10") (pin "32") (pinfunction "P$32_32") (pintype "bidirectional"))
      (node (ref "TP24") (pin "TP") (pinfunction "TP_TP") (pintype "input"))
    )
    (net (code "35") (name "Net-(CON10-P$33)") (class "Default")
      (node (ref "CON10") (pin "33") (pinfunction "P$33_33") (pintype "bidirectional"))
      (node (ref "TP13") (pin "TP") (pinfunction "TP_TP") (pintype "input"))
    )
    (net (code "36") (name "Net-(CON10-P$34)") (class "Default")
      (node (ref "CON10") (pin "34") (pinfunction "P$34_34") (pintype "bidirectional"))
      (node (ref "TP25") (pin "TP") (pinfunction "TP_TP") (pintype "input"))
    )
    (net (code "37") (name "Net-(CON10-P$35)") (class "Default")
      (node (ref "CON10") (pin "35") (pinfunction "P$35_35") (pintype "bidirectional"))
      (node (ref "TP12") (pin "TP") (pinfunction "TP_TP") (pintype "input"))
    )
    (net (code "38") (name "Net-(CON11-P$15)") (class "Default")
      (node (ref "CON11") (pin "15") (pinfunction "P$15_15") (pintype "bidirectional"))
      (node (ref "TP11") (pin "TP") (pinfunction "TP_TP") (pintype "input"))
    )
    (net (code "39") (name "Net-(CON11-P$22)") (class "Default")
      (node (ref "CON11") (pin "22") (pinfunction "P$22_22") (pintype "bidirectional"))
      (node (ref "TP7") (pin "TP") (pinfunction "TP_TP") (pintype "input"))
    )
    (net (code "40") (name "Net-(CON11-P$30)") (class "Default")
      (node (ref "CON11") (pin "30") (pinfunction "P$30_30") (pintype "bidirectional"))
      (node (ref "TP5") (pin "TP") (pinfunction "TP_TP") (pintype "input"))
    )
    (net (code "41") (name "Net-(CON11-P$31)") (class "Default")
      (node (ref "CON11") (pin "31") (pinfunction "P$31_31") (pintype "bidirectional"))
      (node (ref "TP9") (pin "TP") (pinfunction "TP_TP") (pintype "input"))
    )
    (net (code "42") (name "Net-(CON11-P$34)") (class "Default")
      (node (ref "CON11") (pin "34") (pinfunction "P$34_34") (pintype "bidirectional"))
      (node (ref "TP4") (pin "TP") (pinfunction "TP_TP") (pintype "input"))
    )
    (net (code "43") (name "Net-(CON11-P$35)") (class "Default")
      (node (ref "CON11") (pin "35") (pinfunction "P$35_35") (pintype "bidirectional"))
      (node (ref "TP8") (pin "TP") (pinfunction "TP_TP") (pintype "input"))
    )
    (net (code "44") (name "Net-(CON11-P$36)") (class "Default")
      (node (ref "CON11") (pin "36") (pinfunction "P$36_36") (pintype "bidirectional"))
      (node (ref "TP3") (pin "TP") (pinfunction "TP_TP") (pintype "input"))
    )
    (net (code "45") (name "Net-(IC2A-PA4)") (class "Default")
      (node (ref "IC2") (pin "30") (pinfunction "PA4_30") (pintype "bidirectional"))
      (node (ref "R12") (pin "2") (pinfunction "P$2_2") (pintype "passive"))
    )
    (net (code "46") (name "Net-(IC2A-PA17)") (class "Default")
      (node (ref "IC2") (pin "14") (pinfunction "PA17_14") (pintype "bidirectional"))
      (node (ref "IC2") (pin "23") (pinfunction "PA24_23") (pintype "bidirectional"))
      (node (ref "R13") (pin "1") (pinfunction "P$1_1") (pintype "passive"))
    )
    (net (code "47") (name "Net-(IC2A-PA18)") (class "Default")
      (node (ref "IC2") (pin "17") (pinfunction "PA18_17") (pintype "bidirectional"))
      (node (ref "R14") (pin "1") (pinfunction "P$1_1") (pintype "passive"))
    )
    (net (code "48") (name "Net-(IC2D-ERASE)") (class "Default")
      (node (ref "IC2") (pin "43") (pinfunction "ERASE_43") (pintype "bidirectional"))
      (node (ref "R10") (pin "2") (pinfunction "P$2_2") (pintype "passive"))
    )
    (net (code "49") (name "Net-(IC2D-TDI)") (class "Default")
      (node (ref "IC2") (pin "51") (pinfunction "TDI_51") (pintype "bidirectional"))
      (node (ref "R8") (pin "1") (pinfunction "P$1_1") (pintype "passive"))
    )
    (net (code "50") (name "Net-(R3-P$2)") (class "Default")
      (node (ref "LED1") (pin "A") (pinfunction "A_A") (pintype "passive"))
      (node (ref "R3") (pin "2") (pinfunction "P$2_2") (pintype "passive"))
    )
    (net (code "51") (name "Net-(R4-P$2)") (class "Default")
      (node (ref "LED2") (pin "A") (pinfunction "A_A") (pintype "passive"))
      (node (ref "R4") (pin "2") (pinfunction "P$2_2") (pintype "passive"))
    )
    (net (code "52") (name "Net-(R5-P$2)") (class "Default")
      (node (ref "LED3") (pin "A") (pinfunction "A_A") (pintype "passive"))
      (node (ref "R5") (pin "2") (pinfunction "P$2_2") (pintype "passive"))
    )
    (net (code "53") (name "Net-(R15-P$2)") (class "Default")
      (node (ref "R15") (pin "2") (pinfunction "P$2_2") (pintype "passive"))
      (node (ref "SW2") (pin "1") (pinfunction "1_1") (pintype "passive"))
    )
    (net (code "54") (name "Net-(R16-P$2)") (class "Default")
      (node (ref "R16") (pin "2") (pinfunction "P$2_2") (pintype "passive"))
      (node (ref "SW2") (pin "2") (pinfunction "2_2") (pintype "passive"))
    )
    (net (code "55") (name "Net-(R17-P$1)") (class "Default")
      (node (ref "R17") (pin "1") (pinfunction "P$1_1") (pintype "passive"))
      (node (ref "SW4") (pin "P$3") (pinfunction "B1_P$3") (pintype "passive"))
      (node (ref "SW4") (pin "P$4") (pinfunction "B2_P$4") (pintype "passive"))
    )
    (net (code "56") (name "Net-(R23-P$1)") (class "Default")
      (node (ref "R23") (pin "1") (pinfunction "P$1_1") (pintype "passive"))
      (node (ref "SW5") (pin "P$1") (pinfunction "P_P$1") (pintype "passive"))
    )
    (net (code "57") (name "PERI_3V15") (class "Default")
      (node (ref "CON10") (pin "1") (pinfunction "P$1_1") (pintype "bidirectional"))
      (node (ref "CON10") (pin "2") (pinfunction "P$2_2") (pintype "bidirectional"))
      (node (ref "CON10") (pin "3") (pinfunction "P$3_3") (pintype "bidirectional"))
      (node (ref "CON10") (pin "4") (pinfunction "P$4_4") (pintype "bidirectional"))
      (node (ref "R23") (pin "2") (pinfunction "P$2_2") (pintype "passive"))
    )
    (net (code "58") (name "PMIC_PWR") (class "Default")
      (node (ref "CON11") (pin "37") (pinfunction "P$37_37") (pintype "bidirectional"))
      (node (ref "CON11") (pin "38") (pinfunction "P$38_38") (pintype "bidirectional"))
      (node (ref "CON11") (pin "39") (pinfunction "P$39_39") (pintype "bidirectional"))
      (node (ref "CON11") (pin "40") (pinfunction "P$40_40") (pintype "bidirectional"))
      (node (ref "TP10") (pin "TP") (pinfunction "TP_TP") (pintype "input"))
    )
    (net (code "59") (name "PMIC_PWRON") (class "Default")
      (node (ref "C25") (pin "1") (pinfunction "P$1_1") (pintype "passive"))
      (node (ref "CON11") (pin "25") (pinfunction "P$25_25") (pintype "bidirectional"))
      (node (ref "R17") (pin "2") (pinfunction "P$2_2") (pintype "passive"))
      (node (ref "R18") (pin "1") (pinfunction "P$1_1") (pintype "passive"))
    )
    (net (code "60") (name "POR_B") (class "Default")
      (node (ref "CON11") (pin "7") (pinfunction "P$7_7") (pintype "bidirectional"))
      (node (ref "R18") (pin "2") (pinfunction "P$2_2") (pintype "passive"))
      (node (ref "R21") (pin "2") (pinfunction "P$2_2") (pintype "passive"))
    )
    (net (code "61") (name "SPI3_MISO") (class "Default")
      (node (ref "BRD1") (pin "27") (pinfunction "D12/MISO_27") (pintype "bidirectional"))
      (node (ref "CON10") (pin "19") (pinfunction "P$19_19") (pintype "bidirectional"))
    )
    (net (code "62") (name "SPI3_MOSI") (class "Default")
      (node (ref "BRD1") (pin "26") (pinfunction "D11/MOSI_26") (pintype "bidirectional"))
      (node (ref "CON10") (pin "16") (pinfunction "P$16_16") (pintype "bidirectional"))
    )
    (net (code "63") (name "SPI3_SCK") (class "Default")
      (node (ref "BRD1") (pin "28") (pinfunction "D13/SCK_28") (pintype "bidirectional"))
      (node (ref "CON10") (pin "15") (pinfunction "P$15_15") (pintype "bidirectional"))
    )
    (net (code "64") (name "SPI3_SS") (class "Default")
      (node (ref "BRD1") (pin "25") (pinfunction "D10/SS_25") (pintype "bidirectional"))
      (node (ref "CON10") (pin "14") (pinfunction "P$14_14") (pintype "bidirectional"))
    )
    (net (code "65") (name "SW2_1V8") (class "Default")
      (node (ref "CON10") (pin "37") (pinfunction "P$37_37") (pintype "bidirectional"))
      (node (ref "CON10") (pin "38") (pinfunction "P$38_38") (pintype "bidirectional"))
      (node (ref "CON10") (pin "39") (pinfunction "P$39_39") (pintype "bidirectional"))
      (node (ref "CON10") (pin "40") (pinfunction "P$40_40") (pintype "bidirectional"))
      (node (ref "R15") (pin "1") (pinfunction "P$1_1") (pintype "passive"))
      (node (ref "R16") (pin "1") (pinfunction "P$1_1") (pintype "passive"))
    )
    (net (code "66") (name "TGT_NRST") (class "Default")
      (node (ref "IC2") (pin "29") (pinfunction "PA3_29") (pintype "bidirectional"))
      (node (ref "R12") (pin "1") (pinfunction "P$1_1") (pintype "passive"))
      (node (ref "R20") (pin "1") (pinfunction "P$1_1") (pintype "passive"))
      (node (ref "R21") (pin "1") (pinfunction "P$1_1") (pintype "passive"))
      (node (ref "SW1") (pin "P$1") (pinfunction "A1_P$1") (pintype "passive"))
      (node (ref "SW1") (pin "P$2") (pinfunction "A2_P$2") (pintype "passive"))
    )
    (net (code "67") (name "TGT_RXD_A7") (class "Default")
      (node (ref "CON11") (pin "10") (pinfunction "P$10_10") (pintype "bidirectional"))
      (node (ref "IC2") (pin "41") (pinfunction "PA12_41") (pintype "bidirectional"))
    )
    (net (code "68") (name "TGT_RXD_LINUX") (class "Default")
      (node (ref "CON10") (pin "12") (pinfunction "P$12_12") (pintype "bidirectional"))
      (node (ref "IC2") (pin "19") (pinfunction "PA20_19") (pintype "bidirectional"))
    )
    (net (code "69") (name "TGT_SWCLK") (class "Default")
      (node (ref "CON11") (pin "18") (pinfunction "P$18_18") (pintype "bidirectional"))
      (node (ref "IC2") (pin "5") (pinfunction "PA22_5") (pintype "bidirectional"))
      (node (ref "R13") (pin "2") (pinfunction "P$2_2") (pintype "passive"))
    )
    (net (code "70") (name "TGT_SWDIO") (class "Default")
      (node (ref "CON11") (pin "17") (pinfunction "P$17_17") (pintype "bidirectional"))
      (node (ref "IC2") (pin "12") (pinfunction "PA15_12") (pintype "bidirectional"))
      (node (ref "R14") (pin "2") (pinfunction "P$2_2") (pintype "passive"))
    )
    (net (code "71") (name "TGT_SWO") (class "Default")
      (node (ref "CON11") (pin "19") (pinfunction "P$19_19") (pintype "bidirectional"))
      (node (ref "IC2") (pin "21") (pinfunction "PA23_21") (pintype "bidirectional"))
    )
    (net (code "72") (name "TGT_TXD_A7") (class "Default")
      (node (ref "CON11") (pin "8") (pinfunction "P$8_8") (pintype "bidirectional"))
      (node (ref "IC2") (pin "40") (pinfunction "PA11_40") (pintype "bidirectional"))
    )
    (net (code "73") (name "TGT_TXD_LINUX") (class "Default")
      (node (ref "CON10") (pin "11") (pinfunction "P$11_11") (pintype "bidirectional"))
      (node (ref "IC2") (pin "20") (pinfunction "PA21_20") (pintype "bidirectional"))
    )
    (net (code "74") (name "TRST_B") (class "Default")
      (node (ref "CON11") (pin "11") (pinfunction "P$11_11") (pintype "bidirectional"))
      (node (ref "R20") (pin "2") (pinfunction "P$2_2") (pintype "passive"))
    )
    (net (code "75") (name "UART5_RXD") (class "Default")
      (node (ref "BRD1") (pin "15") (pinfunction "D0/RX_15") (pintype "bidirectional"))
      (node (ref "CON11") (pin "23") (pinfunction "P$23_23") (pintype "bidirectional"))
    )
    (net (code "76") (name "UART5_TXD") (class "Default")
      (node (ref "BRD1") (pin "16") (pinfunction "D1/TX_16") (pintype "bidirectional"))
      (node (ref "CON11") (pin "24") (pinfunction "P$24_24") (pintype "bidirectional"))
    )
    (net (code "77") (name "USER_PB1") (class "Default")
      (node (ref "CON10") (pin "9") (pinfunction "P$9_9") (pintype "bidirectional"))
      (node (ref "SW5") (pin "P$2") (pinfunction "S_P$2") (pintype "passive"))
    )
    (net (code "78") (name "VBAT") (class "Default")
      (node (ref "CON11") (pin "1") (pinfunction "P$1_1") (pintype "bidirectional"))
      (node (ref "CON11") (pin "2") (pinfunction "P$2_2") (pintype "bidirectional"))
      (node (ref "CON11") (pin "3") (pinfunction "P$3_3") (pintype "bidirectional"))
      (node (ref "CON11") (pin "4") (pinfunction "P$4_4") (pintype "bidirectional"))
      (node (ref "CON11") (pin "6") (pinfunction "P$6_6") (pintype "bidirectional"))
      (node (ref "R19") (pin "1") (pinfunction "P$1_1") (pintype "passive"))
      (node (ref "R22") (pin "2") (pinfunction "P$2_2") (pintype "passive"))
      (node (ref "TP6") (pin "TP") (pinfunction "TP_TP") (pintype "input"))
    )
    (net (code "79") (name "VBUS_IF") (class "Default")
      (node (ref "CON1") (pin "VBUS") (pinfunction "VBUS_VBUS") (pintype "bidirectional"))
      (node (ref "IC1") (pin "3") (pinfunction "IN_3") (pintype "input"))
    )
    (net (code "80") (name "unconnected-(BRD1-5V-Pad5)") (class "Default")
      (node (ref "BRD1") (pin "5") (pinfunction "5V_5") (pintype "bidirectional"))
    )
    (net (code "81") (name "unconnected-(BRD1-A0-Pad9)") (class "Default")
      (node (ref "BRD1") (pin "9") (pinfunction "A0_9") (pintype "bidirectional"))
    )
    (net (code "82") (name "unconnected-(BRD1-A1-Pad10)") (class "Default")
      (node (ref "BRD1") (pin "10") (pinfunction "A1_10") (pintype "bidirectional"))
    )
    (net (code "83") (name "unconnected-(BRD1-A2-Pad11)") (class "Default")
      (node (ref "BRD1") (pin "11") (pinfunction "A2_11") (pintype "bidirectional"))
    )
    (net (code "84") (name "unconnected-(BRD1-A3-Pad12)") (class "Default")
      (node (ref "BRD1") (pin "12") (pinfunction "A3_12") (pintype "bidirectional"))
    )
    (net (code "85") (name "unconnected-(BRD1-A4-Pad13)") (class "Default")
      (node (ref "BRD1") (pin "13") (pinfunction "A4_13") (pintype "bidirectional"))
    )
    (net (code "86") (name "unconnected-(BRD1-A5-Pad14)") (class "Default")
      (node (ref "BRD1") (pin "14") (pinfunction "A5_14") (pintype "bidirectional"))
    )
    (net (code "87") (name "unconnected-(BRD1-AREF-Pad30)") (class "Default")
      (node (ref "BRD1") (pin "30") (pinfunction "AREF_30") (pintype "bidirectional"))
    )
    (net (code "88") (name "unconnected-(BRD1-D2-Pad17)") (class "Default")
      (node (ref "BRD1") (pin "17") (pinfunction "D2_17") (pintype "bidirectional"))
    )
    (net (code "89") (name "unconnected-(BRD1-D3-Pad18)") (class "Default")
      (node (ref "BRD1") (pin "18") (pinfunction "D3_18") (pintype "bidirectional"))
    )
    (net (code "90") (name "unconnected-(BRD1-D4-Pad19)") (class "Default")
      (node (ref "BRD1") (pin "19") (pinfunction "D4_19") (pintype "bidirectional"))
    )
    (net (code "91") (name "unconnected-(BRD1-D5-Pad20)") (class "Default")
      (node (ref "BRD1") (pin "20") (pinfunction "D5_20") (pintype "bidirectional"))
    )
    (net (code "92") (name "unconnected-(BRD1-D6-Pad21)") (class "Default")
      (node (ref "BRD1") (pin "21") (pinfunction "D6_21") (pintype "bidirectional"))
    )
    (net (code "93") (name "unconnected-(BRD1-D7-Pad22)") (class "Default")
      (node (ref "BRD1") (pin "22") (pinfunction "D7_22") (pintype "bidirectional"))
    )
    (net (code "94") (name "unconnected-(BRD1-D8-Pad23)") (class "Default")
      (node (ref "BRD1") (pin "23") (pinfunction "D8_23") (pintype "bidirectional"))
    )
    (net (code "95") (name "unconnected-(BRD1-D9-Pad24)") (class "Default")
      (node (ref "BRD1") (pin "24") (pinfunction "D9_24") (pintype "bidirectional"))
    )
    (net (code "96") (name "unconnected-(BRD1-GND-Pad29)") (class "Default")
      (node (ref "BRD1") (pin "29") (pinfunction "GND_29") (pintype "bidirectional"))
    )
    (net (code "97") (name "unconnected-(BRD1-IOREF-Pad2)") (class "Default")
      (node (ref "BRD1") (pin "2") (pinfunction "IOREF_2") (pintype "bidirectional"))
    )
    (net (code "98") (name "unconnected-(BRD1-NC-Pad1)") (class "Default")
      (node (ref "BRD1") (pin "1") (pinfunction "NC_1") (pintype "bidirectional"))
    )
    (net (code "99") (name "unconnected-(BRD1-NRESET-Pad3)") (class "Default")
      (node (ref "BRD1") (pin "3") (pinfunction "NRESET_3") (pintype "bidirectional"))
    )
    (net (code "100") (name "unconnected-(BRD1-VIN-Pad8)") (class "Default")
      (node (ref "BRD1") (pin "8") (pinfunction "VIN_8") (pintype "bidirectional"))
    )
    (net (code "101") (name "unconnected-(CON2-KEY-Pad7)") (class "Default")
      (node (ref "CON2") (pin "7") (pinfunction "KEY_7") (pintype "bidirectional"))
    )
    (net (code "102") (name "unconnected-(CON2-NC{slash}TDI-Pad8)") (class "Default")
      (node (ref "CON2") (pin "8") (pinfunction "NC/TDI_8") (pintype "bidirectional"))
    )
    (net (code "103") (name "unconnected-(CON2-SWO{slash}TDO-Pad6)") (class "Default")
      (node (ref "CON2") (pin "6") (pinfunction "SWO/TDO_6") (pintype "bidirectional"))
    )
    (net (code "104") (name "unconnected-(CON10-P$22-Pad22)") (class "Default")
      (node (ref "CON10") (pin "22") (pinfunction "P$22_22") (pintype "bidirectional"))
    )
    (net (code "105") (name "unconnected-(CON11-P$21-Pad21)") (class "Default")
      (node (ref "CON11") (pin "21") (pinfunction "P$21_21") (pintype "bidirectional"))
    )
    (net (code "106") (name "unconnected-(IC2A-PA0-Pad26)") (class "Default")
      (node (ref "IC2") (pin "26") (pinfunction "PA0_26") (pintype "bidirectional"))
    )
    (net (code "107") (name "unconnected-(IC2A-PA1-Pad27)") (class "Default")
      (node (ref "IC2") (pin "27") (pinfunction "PA1_27") (pintype "bidirectional"))
    )
    (net (code "108") (name "unconnected-(IC2A-PA2-Pad28)") (class "Default")
      (node (ref "IC2") (pin "28") (pinfunction "PA2_28") (pintype "bidirectional"))
    )
    (net (code "109") (name "unconnected-(IC2A-PA5-Pad31)") (class "Default")
      (node (ref "IC2") (pin "31") (pinfunction "PA5_31") (pintype "bidirectional"))
    )
    (net (code "110") (name "unconnected-(IC2A-PA6-Pad32)") (class "Default")
      (node (ref "IC2") (pin "32") (pinfunction "PA6_32") (pintype "bidirectional"))
    )
    (net (code "111") (name "unconnected-(IC2A-PA7-Pad33)") (class "Default")
      (node (ref "IC2") (pin "33") (pinfunction "PA7_33") (pintype "bidirectional"))
    )
    (net (code "112") (name "unconnected-(IC2A-PA8-Pad37)") (class "Default")
      (node (ref "IC2") (pin "37") (pinfunction "PA8_37") (pintype "bidirectional"))
    )
    (net (code "113") (name "unconnected-(IC2A-PA9-Pad38)") (class "Default")
      (node (ref "IC2") (pin "38") (pinfunction "PA9_38") (pintype "bidirectional"))
    )
    (net (code "114") (name "unconnected-(IC2A-PA10-Pad39)") (class "Default")
      (node (ref "IC2") (pin "39") (pinfunction "PA10_39") (pintype "bidirectional"))
    )
    (net (code "115") (name "unconnected-(IC2A-PA13-Pad10)") (class "Default")
      (node (ref "IC2") (pin "10") (pinfunction "PA13_10") (pintype "bidirectional"))
    )
    (net (code "116") (name "unconnected-(IC2A-PA14-Pad11)") (class "Default")
      (node (ref "IC2") (pin "11") (pinfunction "PA14_11") (pintype "bidirectional"))
    )
    (net (code "117") (name "unconnected-(IC2A-PA16-Pad13)") (class "Default")
      (node (ref "IC2") (pin "13") (pinfunction "PA16_13") (pintype "bidirectional"))
    )
    (net (code "118") (name "unconnected-(IC2A-PA19-Pad18)") (class "Default")
      (node (ref "IC2") (pin "18") (pinfunction "PA19_18") (pintype "bidirectional"))
    )
    (net (code "119") (name "unconnected-(IC2A-PA25-Pad24)") (class "Default")
      (node (ref "IC2") (pin "24") (pinfunction "PA25_24") (pintype "bidirectional"))
    )
    (net (code "120") (name "unconnected-(IC2A-PA26-Pad25)") (class "Default")
      (node (ref "IC2") (pin "25") (pinfunction "PA26_25") (pintype "bidirectional"))
    )
    (net (code "121") (name "unconnected-(IC2A-PA27-Pad96)") (class "Default")
      (node (ref "IC2") (pin "96") (pinfunction "PA27_96") (pintype "bidirectional"))
    )
    (net (code "122") (name "unconnected-(IC2A-PA30-Pad6)") (class "Default")
      (node (ref "IC2") (pin "6") (pinfunction "PA30_6") (pintype "bidirectional"))
    )
    (net (code "123") (name "unconnected-(IC2B-PB0-Pad90)") (class "Default")
      (node (ref "IC2") (pin "90") (pinfunction "PB0_90") (pintype "bidirectional"))
    )
    (net (code "124") (name "unconnected-(IC2B-PB1-Pad91)") (class "Default")
      (node (ref "IC2") (pin "91") (pinfunction "PB1_91") (pintype "bidirectional"))
    )
    (net (code "125") (name "unconnected-(IC2B-PB2-Pad92)") (class "Default")
      (node (ref "IC2") (pin "92") (pinfunction "PB2_92") (pintype "bidirectional"))
    )
    (net (code "126") (name "unconnected-(IC2B-PB3-Pad7)") (class "Default")
      (node (ref "IC2") (pin "7") (pinfunction "PB3_7") (pintype "bidirectional"))
    )
    (net (code "127") (name "unconnected-(IC2B-PB4-Pad8)") (class "Default")
      (node (ref "IC2") (pin "8") (pinfunction "PB4_8") (pintype "bidirectional"))
    )
    (net (code "128") (name "unconnected-(IC2B-PB5-Pad97)") (class "Default")
      (node (ref "IC2") (pin "97") (pinfunction "PB5_97") (pintype "bidirectional"))
    )
    (net (code "129") (name "unconnected-(IC2B-PB6-Pad98)") (class "Default")
      (node (ref "IC2") (pin "98") (pinfunction "PB6_98") (pintype "bidirectional"))
    )
    (net (code "130") (name "unconnected-(IC2B-PB7-Pad99)") (class "Default")
      (node (ref "IC2") (pin "99") (pinfunction "PB7_99") (pintype "bidirectional"))
    )
    (net (code "131") (name "unconnected-(IC2B-PB8-Pad100)") (class "Default")
      (node (ref "IC2") (pin "100") (pinfunction "PB8_100") (pintype "bidirectional"))
    )
    (net (code "132") (name "unconnected-(IC2B-PB9-Pad71)") (class "Default")
      (node (ref "IC2") (pin "71") (pinfunction "PB9_71") (pintype "bidirectional"))
    )
    (net (code "133") (name "unconnected-(IC2B-PB10-Pad70)") (class "Default")
      (node (ref "IC2") (pin "70") (pinfunction "PB10_70") (pintype "bidirectional"))
    )
    (net (code "134") (name "unconnected-(IC2B-PB11-Pad93)") (class "Default")
      (node (ref "IC2") (pin "93") (pinfunction "PB11_93") (pintype "bidirectional"))
    )
    (net (code "135") (name "unconnected-(IC2B-PB12-Pad94)") (class "Default")
      (node (ref "IC2") (pin "94") (pinfunction "PB12_94") (pintype "bidirectional"))
    )
    (net (code "136") (name "unconnected-(IC2B-PB13-Pad95)") (class "Default")
      (node (ref "IC2") (pin "95") (pinfunction "PB13_95") (pintype "bidirectional"))
    )
    (net (code "137") (name "unconnected-(IC2B-PB14-Pad69)") (class "Default")
      (node (ref "IC2") (pin "69") (pinfunction "PB14_69") (pintype "bidirectional"))
    )
    (net (code "138") (name "unconnected-(IC2B-PB15-Pad16)") (class "Default")
      (node (ref "IC2") (pin "16") (pinfunction "PB15_16") (pintype "bidirectional"))
    )
    (net (code "139") (name "unconnected-(IC2B-PB16-Pad15)") (class "Default")
      (node (ref "IC2") (pin "15") (pinfunction "PB16_15") (pintype "bidirectional"))
    )
    (net (code "140") (name "unconnected-(IC2B-PB17-Pad68)") (class "Default")
      (node (ref "IC2") (pin "68") (pinfunction "PB17_68") (pintype "bidirectional"))
    )
    (net (code "141") (name "unconnected-(IC2B-PB18-Pad67)") (class "Default")
      (node (ref "IC2") (pin "67") (pinfunction "PB18_67") (pintype "bidirectional"))
    )
    (net (code "142") (name "unconnected-(IC2B-PB19-Pad66)") (class "Default")
      (node (ref "IC2") (pin "66") (pinfunction "PB19_66") (pintype "bidirectional"))
    )
    (net (code "143") (name "unconnected-(IC2B-PB20-Pad65)") (class "Default")
      (node (ref "IC2") (pin "65") (pinfunction "PB20_65") (pintype "bidirectional"))
    )
    (net (code "144") (name "unconnected-(IC2B-PB21-Pad64)") (class "Default")
      (node (ref "IC2") (pin "64") (pinfunction "PB21_64") (pintype "bidirectional"))
    )
    (net (code "145") (name "unconnected-(IC2B-PB22-Pad63)") (class "Default")
      (node (ref "IC2") (pin "63") (pinfunction "PB22_63") (pintype "bidirectional"))
    )
    (net (code "146") (name "unconnected-(IC2B-PB23-Pad62)") (class "Default")
      (node (ref "IC2") (pin "62") (pinfunction "PB23_62") (pintype "bidirectional"))
    )
    (net (code "147") (name "unconnected-(IC2B-PB24-Pad58)") (class "Default")
      (node (ref "IC2") (pin "58") (pinfunction "PB24_58") (pintype "bidirectional"))
    )
    (net (code "148") (name "unconnected-(IC2D-JTAGSEL-Pad48)") (class "Default")
      (node (ref "IC2") (pin "48") (pinfunction "JTAGSEL_48") (pintype "bidirectional"))
    )
    (net (code "149") (name "unconnected-(IC2D-TDO{slash}SWO-Pad54)") (class "Default")
      (node (ref "IC2") (pin "54") (pinfunction "TDO/SWO_54") (pintype "bidirectional"))
    )
    (net (code "150") (name "unconnected-(IC2D-TST-Pad44)") (class "Default")
      (node (ref "IC2") (pin "44") (pinfunction "TST_44") (pintype "bidirectional"))
    )
    (net (code "151") (name "unconnected-(IC2D-XIN32-Pad50)") (class "Default")
      (node (ref "IC2") (pin "50") (pinfunction "XIN32_50") (pintype "bidirectional"))
    )
    (net (code "152") (name "unconnected-(IC2D-XOUT32-Pad49)") (class "Default")
      (node (ref "IC2") (pin "49") (pinfunction "XOUT32_49") (pintype "bidirectional"))
    )
  )
)
